# 2403_HDD_ROM_Emulator.net
KiCad netlist of a schematic drawn in Altium Designer
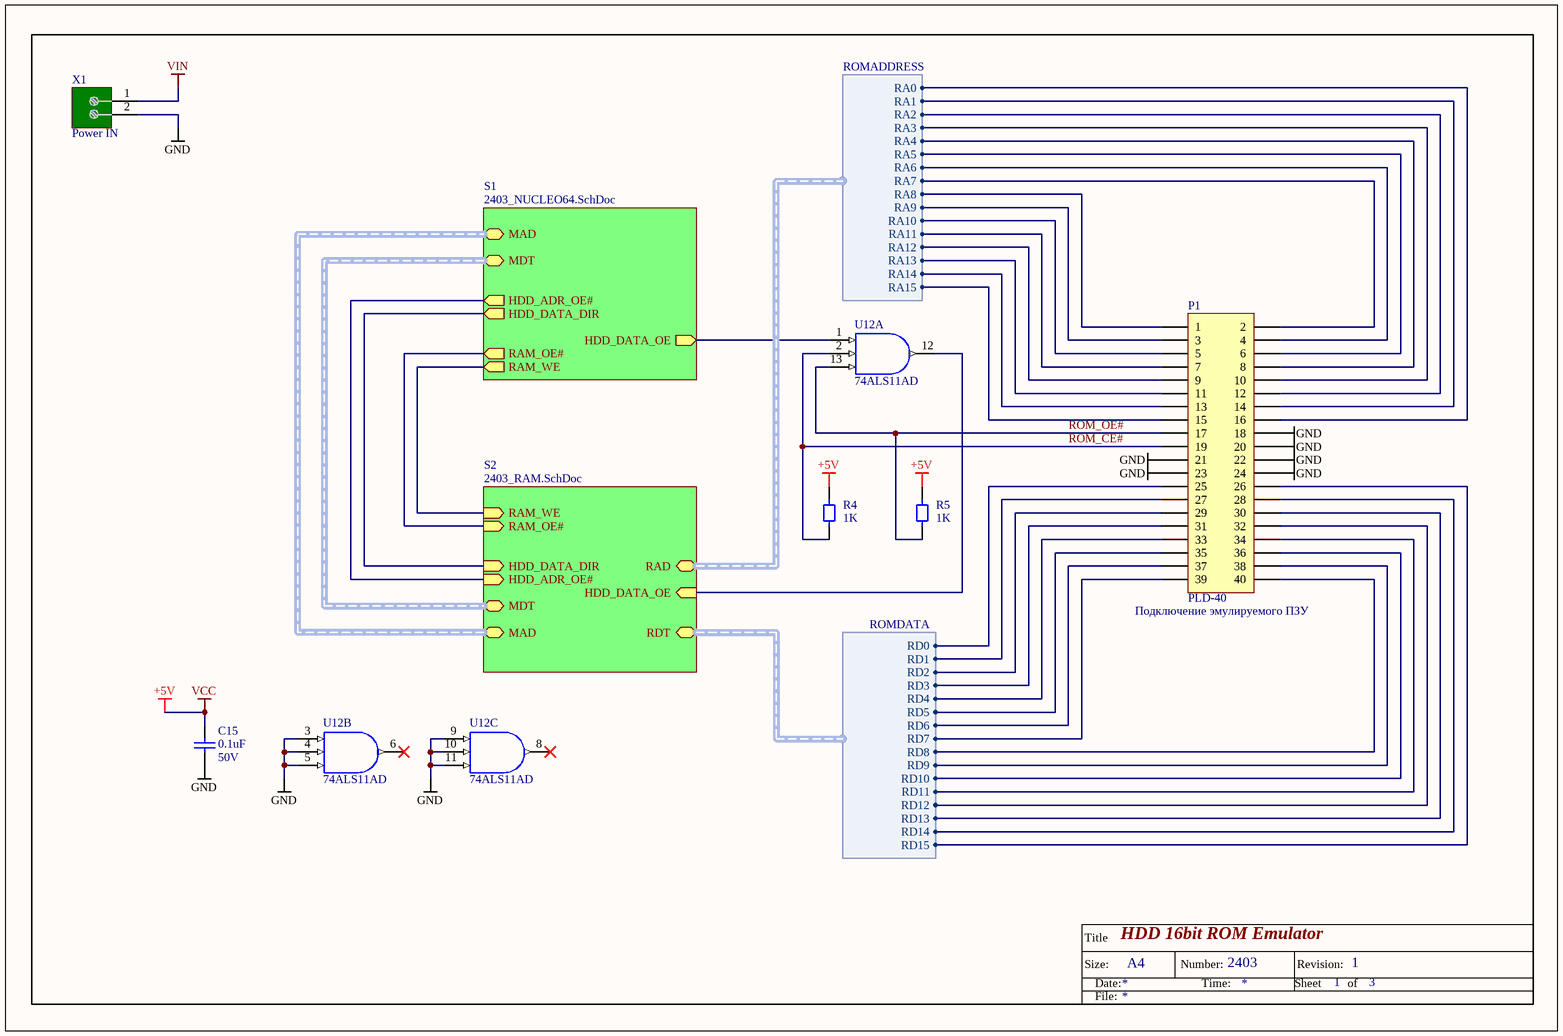
[diagram p0: 2403_HDD_ROM_Emulator.SchDoc]

(export (version "E")
  (design (tool "Eeschema 10.0.6"))
  (components
    (comp (ref "C15")
      (value "0.1uF")
      (footprint "0805_CAPC2013X100N")
      (description "Capacitor SMD")
      (fields (field (name "RATED VOLTAGE") "50V") (field (name "PUBLISHER") "SY"))
      (libsource (lib "Prj24_Library") (part "Cap SMD"))
    )
    (comp (ref "P1")
      (value "PLD-40")
      (footprint "PLD40_3M_2540-6002RB")
      (description "40pin 2.54mm pitch plug")
      (fields (field (name "PUBLISHER") "SY"))
      (libsource (lib "Prj24_Library") (part "PLD-40"))
    )
    (comp (ref "R4")
      (value "1K")
      (footprint "0805_RESC2013X84N")
      (description "SMD Resistor")
      (fields (field (name "TOLERANCE") "5%") (field (name "POWER") "0.1W") (field (name "PUBLISHER") "SY"))
      (libsource (lib "Prj24_Library") (part "Resistor SMD L"))
    )
    (comp (ref "R5")
      (value "1K")
      (footprint "0805_RESC2013X84N")
      (description "SMD Resistor")
      (fields (field (name "TOLERANCE") "5%") (field (name "POWER") "0.1W") (field (name "PUBLISHER") "SY"))
      (libsource (lib "Prj24_Library") (part "Resistor SMD L"))
    )
    (comp (ref "U12")
      (value "74ALS11AD")
      (footprint "DIP14-300")
      (description "К1533ЛИ3 Triple 3-Input Positive-AND Gate")
      (fields (field (name "PUBLISHER") "SY"))
      (libsource (lib "Prj24_Library") (part "74ALS11AD"))
    )
    (comp (ref "X1")
      (value "DG306-5.0 2")
      (footprint "PHOENIX_3.5mm")
      (description "2pin connector")
      (fields (field (name "CONNECTIONNAME") "Power IN") (field (name "PUBLISHER") "SY"))
      (libsource (lib "Prj24_Library") (part "CON_Plug2"))
    )
  )
  (nets
    (net (code "3") (name "+5V") (class "Default")
      (node (ref "C15") (pin "2") (pinfunction "2_2") (pintype "passive"))
      (node (ref "R4") (pin "2") (pinfunction "2_2") (pintype "passive"))
      (node (ref "R5") (pin "2") (pinfunction "2_2") (pintype "passive"))
      (node (ref "U12") (pin "14") (pinfunction "VCC_14") (pintype "power_in"))
    )
    (net (code "6") (name "/HDD_DATA_OE") (class "Default")
      (node (ref "U12") (pin "12") (pinfunction "Y_12") (pintype "output"))
    )
    (net (code "7") (name "/HDD_DATA_OE_1") (class "Default")
      (node (ref "U12") (pin "1") (pinfunction "A_1") (pintype "input"))
    )
    (net (code "10") (name "/RA0") (class "Default")
      (node (ref "P1") (pin "16") (pinfunction "16_16") (pintype "passive"))
    )
    (net (code "11") (name "/RA1") (class "Default")
      (node (ref "P1") (pin "14") (pinfunction "14_14") (pintype "passive"))
    )
    (net (code "12") (name "/RA2") (class "Default")
      (node (ref "P1") (pin "12") (pinfunction "12_12") (pintype "passive"))
    )
    (net (code "13") (name "/RA3") (class "Default")
      (node (ref "P1") (pin "10") (pinfunction "10_10") (pintype "passive"))
    )
    (net (code "14") (name "/RA4") (class "Default")
      (node (ref "P1") (pin "8") (pinfunction "8_8") (pintype "passive"))
    )
    (net (code "15") (name "/RA5") (class "Default")
      (node (ref "P1") (pin "6") (pinfunction "6_6") (pintype "passive"))
    )
    (net (code "16") (name "/RA6") (class "Default")
      (node (ref "P1") (pin "4") (pinfunction "4_4") (pintype "passive"))
    )
    (net (code "17") (name "/RA7") (class "Default")
      (node (ref "P1") (pin "2") (pinfunction "2_2") (pintype "passive"))
    )
    (net (code "18") (name "/RA8") (class "Default")
      (node (ref "P1") (pin "1") (pinfunction "1_1") (pintype "passive"))
    )
    (net (code "19") (name "/RA9") (class "Default")
      (node (ref "P1") (pin "3") (pinfunction "3_3") (pintype "passive"))
    )
    (net (code "20") (name "/RA10") (class "Default")
      (node (ref "P1") (pin "5") (pinfunction "5_5") (pintype "passive"))
    )
    (net (code "21") (name "/RA11") (class "Default")
      (node (ref "P1") (pin "7") (pinfunction "7_7") (pintype "passive"))
    )
    (net (code "22") (name "/RA12") (class "Default")
      (node (ref "P1") (pin "9") (pinfunction "9_9") (pintype "passive"))
    )
    (net (code "23") (name "/RA13") (class "Default")
      (node (ref "P1") (pin "11") (pinfunction "11_11") (pintype "passive"))
    )
    (net (code "24") (name "/RA14") (class "Default")
      (node (ref "P1") (pin "13") (pinfunction "13_13") (pintype "passive"))
    )
    (net (code "25") (name "/RA15") (class "Default")
      (node (ref "P1") (pin "15") (pinfunction "15_15") (pintype "passive"))
    )
    (net (code "28") (name "/RD0") (class "Default")
      (node (ref "P1") (pin "25") (pinfunction "25_25") (pintype "passive"))
    )
    (net (code "29") (name "/RD1") (class "Default")
      (node (ref "P1") (pin "27") (pinfunction "27_27") (pintype "passive"))
    )
    (net (code "30") (name "/RD2") (class "Default")
      (node (ref "P1") (pin "29") (pinfunction "29_29") (pintype "passive"))
    )
    (net (code "31") (name "/RD3") (class "Default")
      (node (ref "P1") (pin "31") (pinfunction "31_31") (pintype "passive"))
    )
    (net (code "32") (name "/RD4") (class "Default")
      (node (ref "P1") (pin "33") (pinfunction "33_33") (pintype "passive"))
    )
    (net (code "33") (name "/RD5") (class "Default")
      (node (ref "P1") (pin "35") (pinfunction "35_35") (pintype "passive"))
    )
    (net (code "34") (name "/RD6") (class "Default")
      (node (ref "P1") (pin "37") (pinfunction "37_37") (pintype "passive"))
    )
    (net (code "35") (name "/RD7") (class "Default")
      (node (ref "P1") (pin "39") (pinfunction "39_39") (pintype "passive"))
    )
    (net (code "36") (name "/RD8") (class "Default")
      (node (ref "P1") (pin "40") (pinfunction "40_40") (pintype "passive"))
    )
    (net (code "37") (name "/RD9") (class "Default")
      (node (ref "P1") (pin "38") (pinfunction "38_38") (pintype "passive"))
    )
    (net (code "38") (name "/RD10") (class "Default")
      (node (ref "P1") (pin "36") (pinfunction "36_36") (pintype "passive"))
    )
    (net (code "39") (name "/RD11") (class "Default")
      (node (ref "P1") (pin "34") (pinfunction "34_34") (pintype "passive"))
    )
    (net (code "40") (name "/RD12") (class "Default")
      (node (ref "P1") (pin "32") (pinfunction "32_32") (pintype "passive"))
    )
    (net (code "41") (name "/RD13") (class "Default")
      (node (ref "P1") (pin "30") (pinfunction "30_30") (pintype "passive"))
    )
    (net (code "42") (name "/RD14") (class "Default")
      (node (ref "P1") (pin "28") (pinfunction "28_28") (pintype "passive"))
    )
    (net (code "43") (name "/RD15") (class "Default")
      (node (ref "P1") (pin "26") (pinfunction "26_26") (pintype "passive"))
    )
    (net (code "44") (name "/ROM_CE#") (class "Default")
      (node (ref "P1") (pin "19") (pinfunction "19_19") (pintype "passive"))
      (node (ref "R4") (pin "1") (pinfunction "1_1") (pintype "passive"))
      (node (ref "U12") (pin "2") (pinfunction "B_2") (pintype "input"))
    )
    (net (code "45") (name "/ROM_OE#") (class "Default")
      (node (ref "P1") (pin "17") (pinfunction "17_17") (pintype "passive"))
      (node (ref "R5") (pin "1") (pinfunction "1_1") (pintype "passive"))
      (node (ref "U12") (pin "13") (pinfunction "C_13") (pintype "input"))
    )
    (net (code "48") (name "GND") (class "Default")
      (node (ref "C15") (pin "1") (pinfunction "1_1") (pintype "passive"))
      (node (ref "P1") (pin "18") (pinfunction "18_18") (pintype "passive"))
      (node (ref "P1") (pin "20") (pinfunction "20_20") (pintype "passive"))
      (node (ref "P1") (pin "21") (pinfunction "21_21") (pintype "passive"))
      (node (ref "P1") (pin "22") (pinfunction "22_22") (pintype "passive"))
      (node (ref "P1") (pin "23") (pinfunction "23_23") (pintype "passive"))
      (node (ref "P1") (pin "24") (pinfunction "24_24") (pintype "passive"))
      (node (ref "U12") (pin "10") (pinfunction "B_10") (pintype "input"))
      (node (ref "U12") (pin "11") (pinfunction "C_11") (pintype "input"))
      (node (ref "U12") (pin "3") (pinfunction "A_3") (pintype "input"))
      (node (ref "U12") (pin "4") (pinfunction "B_4") (pintype "input"))
      (node (ref "U12") (pin "5") (pinfunction "C_5") (pintype "input"))
      (node (ref "U12") (pin "7") (pinfunction "GND_7") (pintype "power_in"))
      (node (ref "U12") (pin "9") (pinfunction "A_9") (pintype "input"))
      (node (ref "X1") (pin "2") (pinfunction "2_2") (pintype "passive"))
    )
    (net (code "49") (name "VIN") (class "Default")
      (node (ref "X1") (pin "1") (pinfunction "1_1") (pintype "passive"))
    )
    (net (code "50") (name "unconnected-(U12B-Y-Pad6)") (class "Default")
      (node (ref "U12") (pin "6") (pinfunction "Y_6") (pintype "output+no_connect"))
    )
    (net (code "51") (name "unconnected-(U12C-Y-Pad8)") (class "Default")
      (node (ref "U12") (pin "8") (pinfunction "Y_8") (pintype "output+no_connect"))
    )
  )
)
